# cs301_3.net
KiCad netlist of a schematic drawn in Altium Designer
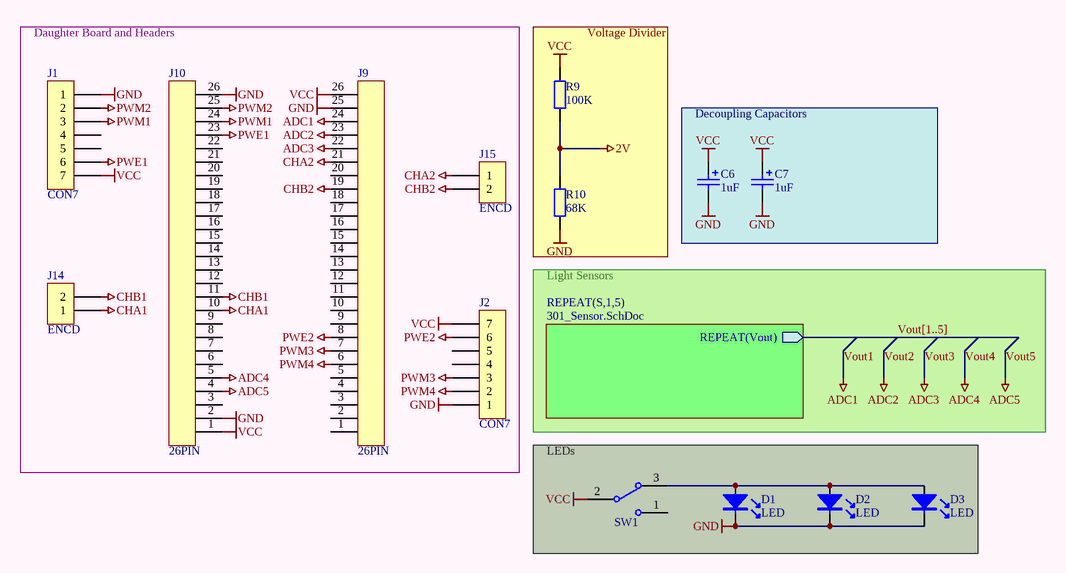
[diagram p0: cs301_3.SchDoc]

(export (version "E")
  (design (tool "Eeschema 10.0.6"))
  (components
    (comp (ref "C6")
      (value "1uF")
      (footprint "ece-RAD-CAP--5X6.8")
      (description "Polarized Capacitor (Radial)")
      (fields (field (name "MANUFACTURER") "Generic Components") (field (name "PUBLISHER") "Altium Limited"))
      (libsource (lib "ece components") (part "CAP 1-10uF TH"))
    )
    (comp (ref "C7")
      (value "1uF")
      (footprint "ece-RAD-CAP--5X6.8")
      (description "Polarized Capacitor (Radial)")
      (fields (field (name "MANUFACTURER") "Generic Components") (field (name "PUBLISHER") "Altium Limited"))
      (libsource (lib "ece components") (part "CAP 1-10uF TH"))
    )
    (comp (ref "D1") (value "LED") (footprint "LED0.1/5MM") (libsource (lib "COMSYS301_2013") (part "LED")))
    (comp (ref "D2") (value "LED") (footprint "LED0.1/5MM") (libsource (lib "COMSYS301_2013") (part "LED")))
    (comp (ref "D3") (value "LED") (footprint "LED0.1/5MM") (libsource (lib "COMSYS301_2013") (part "LED")))
    (comp (ref "J1")
      (value "CON7")
      (footprint "SIP7")
      (description "Connector")
      (libsource (lib "Miscellaneous Devices") (part "CON7"))
    )
    (comp (ref "J2")
      (value "CON7")
      (footprint "SIP7")
      (description "Connector")
      (libsource (lib "") (part "CON7_1"))
    )
    (comp (ref "J9")
      (value "26PIN")
      (footprint "SIP26")
      (libsource (lib "Miscellaneous Devices") (part "26PIN"))
    )
    (comp (ref "J10") (value "26PIN") (footprint "SIP26") (libsource (lib "") (part "26PIN_1")))
    (comp (ref "J14")
      (value "ENCD")
      (footprint "sip2")
      (description "Connector")
      (libsource (lib "Miscellaneous Devices") (part "CON2"))
    )
    (comp (ref "J15")
      (value "ENCD")
      (footprint "sip2")
      (description "Connector")
      (libsource (lib "") (part "CON2_1"))
    )
    (comp (ref "R9")
      (value "100K")
      (footprint "RESC2012-0805SM")
      (description "SM resistor")
      (libsource (lib "ece components") (part "Res SM 0805"))
    )
    (comp (ref "R10")
      (value "68K")
      (footprint "RESC2012-0805SM")
      (description "SM resistor")
      (libsource (lib "ece components") (part "Res SM 0805"))
    )
    (comp (ref "SW1")
      (value "SW")
      (footprint "ece-sw-SPDT")
      (description "PCB mountabel switch")
      (libsource (lib "ece components") (part "switch-SPDT"))
    )
  )
  (nets
    (net (code "3") (name "2V") (class "Default")
      (node (ref "R10") (pin "2") (pinfunction "2_2") (pintype "passive"))
      (node (ref "R9") (pin "1") (pinfunction "1_1") (pintype "passive"))
    )
    (net (code "4") (name "ADC1") (class "Default")
      (node (ref "J9") (pin "24") (pinfunction "24_24") (pintype "passive"))
    )
    (net (code "5") (name "ADC2") (class "Default")
      (node (ref "J9") (pin "23") (pinfunction "23_23") (pintype "passive"))
    )
    (net (code "6") (name "ADC3") (class "Default")
      (node (ref "J9") (pin "22") (pinfunction "22_22") (pintype "passive"))
    )
    (net (code "7") (name "ADC4") (class "Default")
      (node (ref "J10") (pin "5") (pinfunction "5_5") (pintype "passive"))
    )
    (net (code "8") (name "ADC5") (class "Default")
      (node (ref "J10") (pin "4") (pinfunction "4_4") (pintype "passive"))
    )
    (net (code "9") (name "CHA1") (class "Default")
      (node (ref "J10") (pin "10") (pinfunction "10_10") (pintype "passive"))
      (node (ref "J14") (pin "1") (pinfunction "1_1") (pintype "passive"))
    )
    (net (code "10") (name "CHA2") (class "Default")
      (node (ref "J15") (pin "1") (pinfunction "1_1") (pintype "passive"))
      (node (ref "J9") (pin "21") (pinfunction "21_21") (pintype "passive"))
    )
    (net (code "11") (name "CHB1") (class "Default")
      (node (ref "J10") (pin "11") (pinfunction "11_11") (pintype "passive"))
      (node (ref "J14") (pin "2") (pinfunction "2_2") (pintype "passive"))
    )
    (net (code "12") (name "CHB2") (class "Default")
      (node (ref "J15") (pin "2") (pinfunction "2_2") (pintype "passive"))
      (node (ref "J9") (pin "19") (pinfunction "19_19") (pintype "passive"))
    )
    (net (code "13") (name "GND") (class "Default")
      (node (ref "C6") (pin "2") (pinfunction "2_2") (pintype "passive"))
      (node (ref "C7") (pin "2") (pinfunction "2_2") (pintype "passive"))
      (node (ref "D1") (pin "K") (pinfunction "2_K") (pintype "passive"))
      (node (ref "D2") (pin "K") (pinfunction "2_K") (pintype "passive"))
      (node (ref "D3") (pin "K") (pinfunction "2_K") (pintype "passive"))
      (node (ref "J1") (pin "1") (pinfunction "1_1") (pintype "passive"))
      (node (ref "J10") (pin "2") (pinfunction "2_2") (pintype "passive"))
      (node (ref "J10") (pin "26") (pinfunction "26_26") (pintype "passive"))
      (node (ref "J2") (pin "1") (pinfunction "1_1") (pintype "passive"))
      (node (ref "J9") (pin "25") (pinfunction "25_25") (pintype "passive"))
      (node (ref "R10") (pin "1") (pinfunction "1_1") (pintype "passive"))
    )
    (net (code "14") (name "Net-(D1-1)") (class "Default")
      (node (ref "D1") (pin "A") (pinfunction "1_A") (pintype "passive"))
      (node (ref "D2") (pin "A") (pinfunction "1_A") (pintype "passive"))
      (node (ref "D3") (pin "A") (pinfunction "1_A") (pintype "passive"))
      (node (ref "SW1") (pin "3") (pinfunction "3_3") (pintype "passive"))
    )
    (net (code "15") (name "PWE1") (class "Default")
      (node (ref "J1") (pin "6") (pinfunction "6_6") (pintype "passive"))
      (node (ref "J10") (pin "23") (pinfunction "23_23") (pintype "passive"))
    )
    (net (code "16") (name "PWE2") (class "Default")
      (node (ref "J2") (pin "6") (pinfunction "6_6") (pintype "passive"))
      (node (ref "J9") (pin "8") (pinfunction "8_8") (pintype "passive"))
    )
    (net (code "17") (name "PWM1") (class "Default")
      (node (ref "J1") (pin "3") (pinfunction "3_3") (pintype "passive"))
      (node (ref "J10") (pin "24") (pinfunction "24_24") (pintype "passive"))
    )
    (net (code "18") (name "PWM2") (class "Default")
      (node (ref "J1") (pin "2") (pinfunction "2_2") (pintype "passive"))
      (node (ref "J10") (pin "25") (pinfunction "25_25") (pintype "passive"))
    )
    (net (code "19") (name "PWM3") (class "Default")
      (node (ref "J2") (pin "3") (pinfunction "3_3") (pintype "passive"))
      (node (ref "J9") (pin "7") (pinfunction "7_7") (pintype "passive"))
    )
    (net (code "20") (name "PWM4") (class "Default")
      (node (ref "J2") (pin "2") (pinfunction "2_2") (pintype "passive"))
      (node (ref "J9") (pin "6") (pinfunction "6_6") (pintype "passive"))
    )
    (net (code "21") (name "VCC") (class "Default")
      (node (ref "C6") (pin "1") (pinfunction "1_1") (pintype "passive"))
      (node (ref "C7") (pin "1") (pinfunction "1_1") (pintype "passive"))
      (node (ref "J1") (pin "7") (pinfunction "7_7") (pintype "passive"))
      (node (ref "J10") (pin "1") (pinfunction "1_1") (pintype "passive"))
      (node (ref "J2") (pin "7") (pinfunction "7_7") (pintype "passive"))
      (node (ref "J9") (pin "26") (pinfunction "26_26") (pintype "passive"))
      (node (ref "R9") (pin "2") (pinfunction "2_2") (pintype "passive"))
      (node (ref "SW1") (pin "2") (pinfunction "2_2") (pintype "passive"))
    )
    (net (code "22") (name "unconnected-(J1-Pad4)") (class "Default")
      (node (ref "J1") (pin "4") (pinfunction "4_4") (pintype "passive"))
    )
    (net (code "23") (name "unconnected-(J1-Pad5)") (class "Default")
      (node (ref "J1") (pin "5") (pinfunction "5_5") (pintype "passive"))
    )
    (net (code "24") (name "unconnected-(J2-Pad4)") (class "Default")
      (node (ref "J2") (pin "4") (pinfunction "4_4") (pintype "passive"))
    )
    (net (code "25") (name "unconnected-(J2-Pad5)") (class "Default")
      (node (ref "J2") (pin "5") (pinfunction "5_5") (pintype "passive"))
    )
    (net (code "26") (name "unconnected-(J9-Pad1)") (class "Default")
      (node (ref "J9") (pin "1") (pinfunction "1_1") (pintype "passive"))
    )
    (net (code "27") (name "unconnected-(J9-Pad2)") (class "Default")
      (node (ref "J9") (pin "2") (pinfunction "2_2") (pintype "passive"))
    )
    (net (code "28") (name "unconnected-(J9-Pad3)") (class "Default")
      (node (ref "J9") (pin "3") (pinfunction "3_3") (pintype "passive"))
    )
    (net (code "29") (name "unconnected-(J9-Pad4)") (class "Default")
      (node (ref "J9") (pin "4") (pinfunction "4_4") (pintype "passive"))
    )
    (net (code "30") (name "unconnected-(J9-Pad5)") (class "Default")
      (node (ref "J9") (pin "5") (pinfunction "5_5") (pintype "passive"))
    )
    (net (code "31") (name "unconnected-(J9-Pad9)") (class "Default")
      (node (ref "J9") (pin "9") (pinfunction "9_9") (pintype "passive"))
    )
    (net (code "32") (name "unconnected-(J9-Pad10)") (class "Default")
      (node (ref "J9") (pin "10") (pinfunction "10_10") (pintype "passive"))
    )
    (net (code "33") (name "unconnected-(J9-Pad11)") (class "Default")
      (node (ref "J9") (pin "11") (pinfunction "11_11") (pintype "passive"))
    )
    (net (code "34") (name "unconnected-(J9-Pad12)") (class "Default")
      (node (ref "J9") (pin "12") (pinfunction "12_12") (pintype "passive"))
    )
    (net (code "35") (name "unconnected-(J9-Pad13)") (class "Default")
      (node (ref "J9") (pin "13") (pinfunction "13_13") (pintype "passive"))
    )
    (net (code "36") (name "unconnected-(J9-Pad14)") (class "Default")
      (node (ref "J9") (pin "14") (pinfunction "14_14") (pintype "passive"))
    )
    (net (code "37") (name "unconnected-(J9-Pad15)") (class "Default")
      (node (ref "J9") (pin "15") (pinfunction "15_15") (pintype "passive"))
    )
    (net (code "38") (name "unconnected-(J9-Pad16)") (class "Default")
      (node (ref "J9") (pin "16") (pinfunction "16_16") (pintype "passive"))
    )
    (net (code "39") (name "unconnected-(J9-Pad17)") (class "Default")
      (node (ref "J9") (pin "17") (pinfunction "17_17") (pintype "passive"))
    )
    (net (code "40") (name "unconnected-(J9-Pad18)") (class "Default")
      (node (ref "J9") (pin "18") (pinfunction "18_18") (pintype "passive"))
    )
    (net (code "41") (name "unconnected-(J9-Pad20)") (class "Default")
      (node (ref "J9") (pin "20") (pinfunction "20_20") (pintype "passive"))
    )
    (net (code "42") (name "unconnected-(J10-Pad3)") (class "Default")
      (node (ref "J10") (pin "3") (pinfunction "3_3") (pintype "passive"))
    )
    (net (code "43") (name "unconnected-(J10-Pad6)") (class "Default")
      (node (ref "J10") (pin "6") (pinfunction "6_6") (pintype "passive"))
    )
    (net (code "44") (name "unconnected-(J10-Pad7)") (class "Default")
      (node (ref "J10") (pin "7") (pinfunction "7_7") (pintype "passive"))
    )
    (net (code "45") (name "unconnected-(J10-Pad8)") (class "Default")
      (node (ref "J10") (pin "8") (pinfunction "8_8") (pintype "passive"))
    )
    (net (code "46") (name "unconnected-(J10-Pad9)") (class "Default")
      (node (ref "J10") (pin "9") (pinfunction "9_9") (pintype "passive"))
    )
    (net (code "47") (name "unconnected-(J10-Pad12)") (class "Default")
      (node (ref "J10") (pin "12") (pinfunction "12_12") (pintype "passive"))
    )
    (net (code "48") (name "unconnected-(J10-Pad13)") (class "Default")
      (node (ref "J10") (pin "13") (pinfunction "13_13") (pintype "passive"))
    )
    (net (code "49") (name "unconnected-(J10-Pad14)") (class "Default")
      (node (ref "J10") (pin "14") (pinfunction "14_14") (pintype "passive"))
    )
    (net (code "50") (name "unconnected-(J10-Pad15)") (class "Default")
      (node (ref "J10") (pin "15") (pinfunction "15_15") (pintype "passive"))
    )
    (net (code "51") (name "unconnected-(J10-Pad16)") (class "Default")
      (node (ref "J10") (pin "16") (pinfunction "16_16") (pintype "passive"))
    )
    (net (code "52") (name "unconnected-(J10-Pad17)") (class "Default")
      (node (ref "J10") (pin "17") (pinfunction "17_17") (pintype "passive"))
    )
    (net (code "53") (name "unconnected-(J10-Pad18)") (class "Default")
      (node (ref "J10") (pin "18") (pinfunction "18_18") (pintype "passive"))
    )
    (net (code "54") (name "unconnected-(J10-Pad19)") (class "Default")
      (node (ref "J10") (pin "19") (pinfunction "19_19") (pintype "passive"))
    )
    (net (code "55") (name "unconnected-(J10-Pad20)") (class "Default")
      (node (ref "J10") (pin "20") (pinfunction "20_20") (pintype "passive"))
    )
    (net (code "56") (name "unconnected-(J10-Pad21)") (class "Default")
      (node (ref "J10") (pin "21") (pinfunction "21_21") (pintype "passive"))
    )
    (net (code "57") (name "unconnected-(J10-Pad22)") (class "Default")
      (node (ref "J10") (pin "22") (pinfunction "22_22") (pintype "passive"))
    )
    (net (code "58") (name "unconnected-(SW1-Pad1)") (class "Default")
      (node (ref "SW1") (pin "1") (pinfunction "1_1") (pintype "passive"))
    )
  )
)
